# Escorna_CPU_2_20.net
KiCad netlist of a schematic drawn in EAGLE
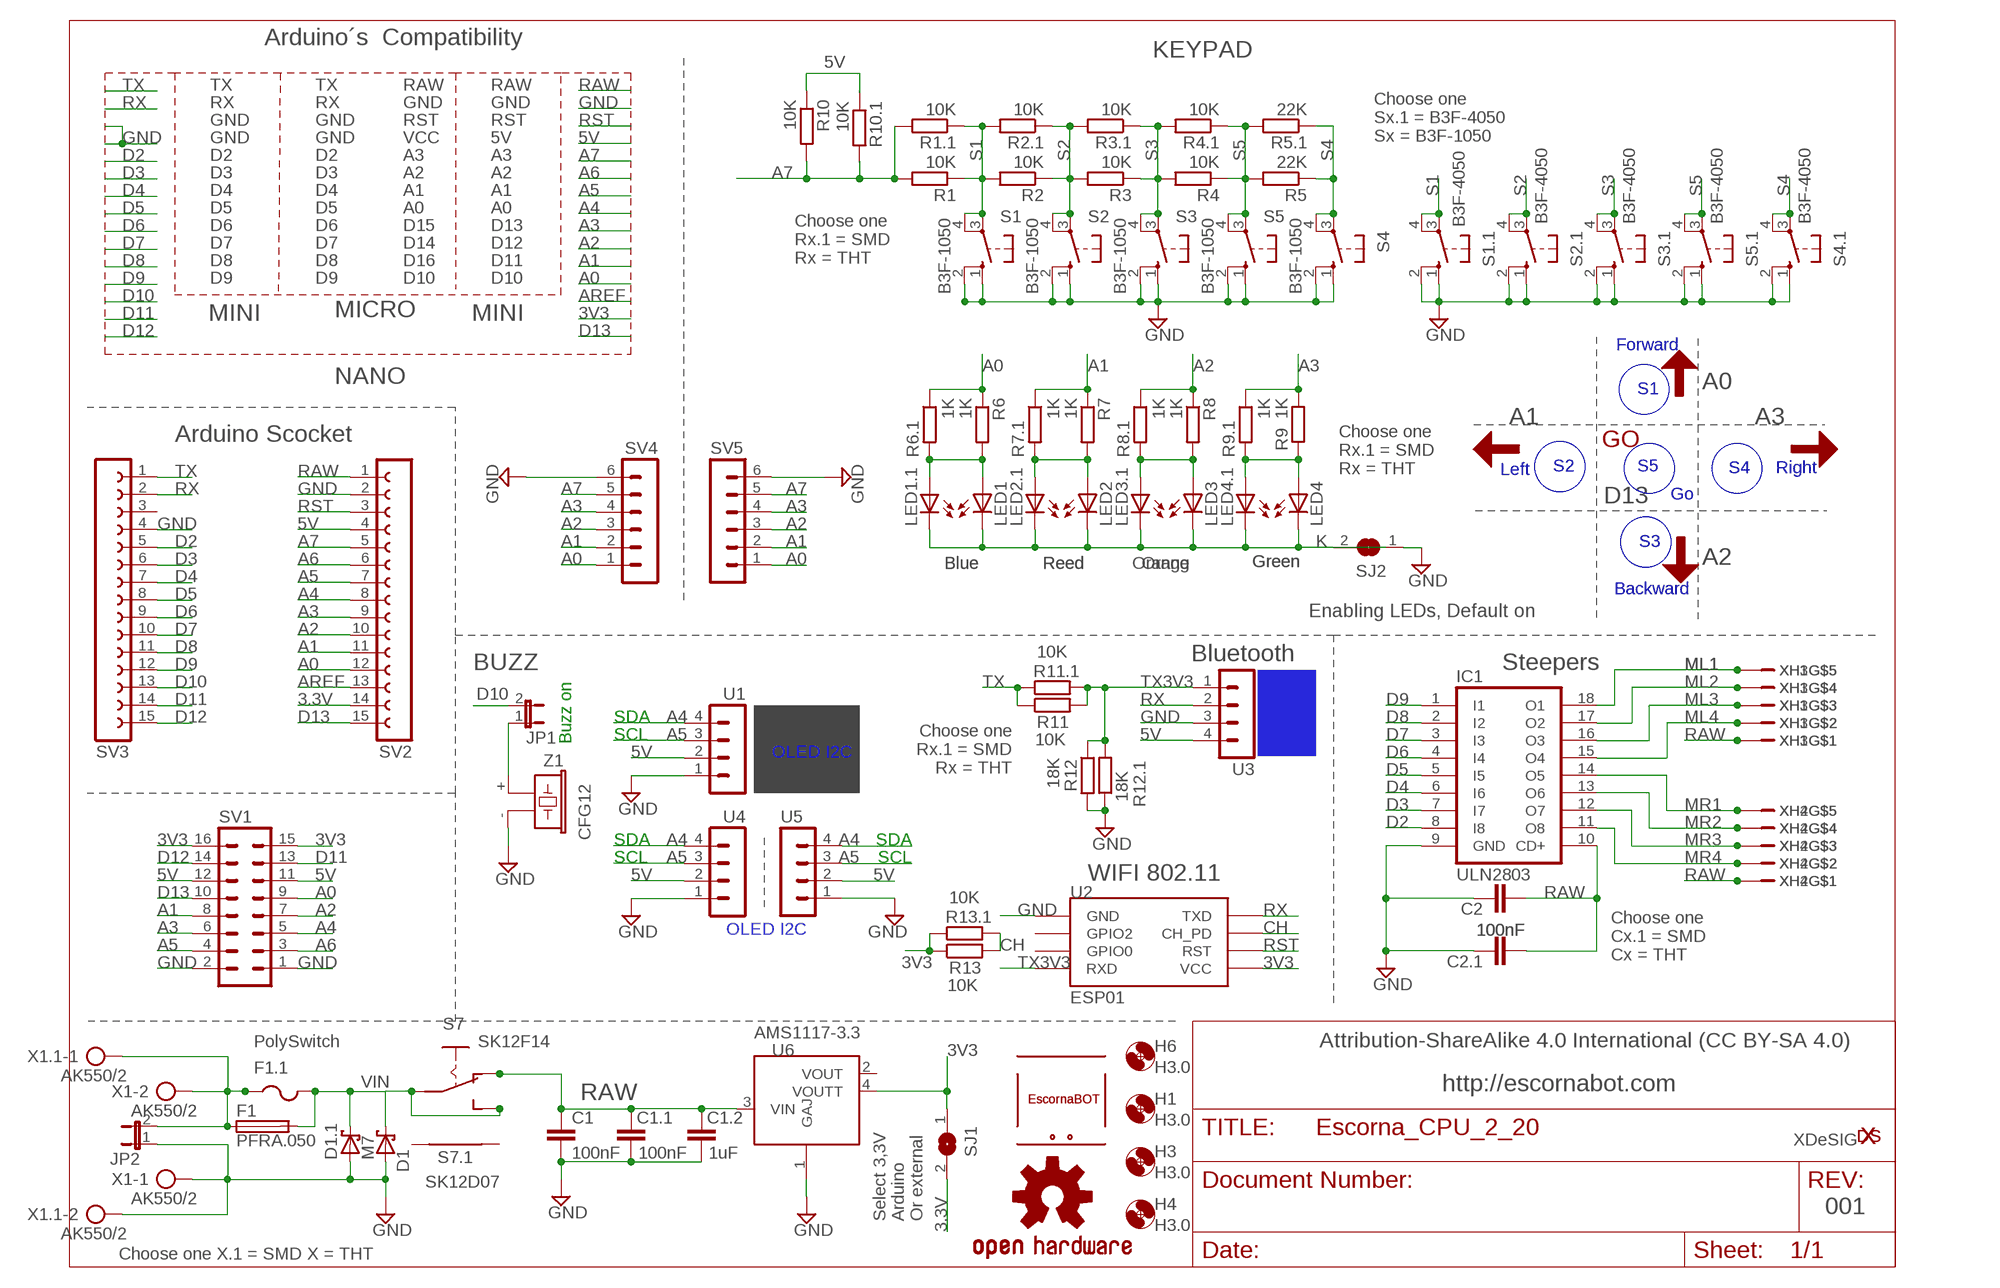
[diagram p0: schematic, sheet 1]

(export (version "E")
  (design (tool "Eeschema 10.0.6"))
  (components
    (comp (ref "C1")
      (value "100nF")
      (footprint "eagle-import:C025-025X050")
      (libsource (lib "eagle-import") (part "C-EU025-025X050"))
    )
    (comp (ref "C1.1")
      (value "100nF")
      (footprint "eagle-import:C0603K")
      (libsource (lib "eagle-import") (part "C-EUC0603K"))
    )
    (comp (ref "C1.2")
      (value "1uF")
      (footprint "eagle-import:C0603K")
      (libsource (lib "eagle-import") (part "C-EUC0603K"))
    )
    (comp (ref "C2")
      (value "100nF")
      (footprint "eagle-import:C025-025X050")
      (libsource (lib "eagle-import") (part "C-EU025-025X050"))
    )
    (comp (ref "C2.1")
      (value "100nF")
      (footprint "eagle-import:C0603K")
      (libsource (lib "eagle-import") (part "C-EUC0603K"))
    )
    (comp (ref "D1")
      (value "1N5817")
      (footprint "eagle-import:DO41-10")
      (libsource (lib "eagle-import") (part "P4KEXX"))
    )
    (comp (ref "D1.1")
      (value "M7")
      (footprint "eagle-import:SMA")
      (libsource (lib "eagle-import") (part "SCHOTTKY-DIODESMA"))
    )
    (comp (ref "ESC1")
      (value "ESCORNABOT")
      (footprint "eagle-import:ESCORNA_PEQUE")
      (libsource (lib "eagle-import") (part "ESCORNABOT"))
    )
    (comp (ref "ESC2")
      (value "ESCORNABOT")
      (footprint "eagle-import:ESCORNA_PEQUE")
      (libsource (lib "eagle-import") (part "ESCORNABOT"))
    )
    (comp (ref "F1")
      (value "PFRA.050")
      (footprint "eagle-import:TE5")
      (libsource (lib "eagle-import") (part "FUSETE5"))
    )
    (comp (ref "F1.1")
      (value "PolySwitch")
      (footprint "eagle-import:R1206")
      (libsource (lib "eagle-import") (part "PTCFUSE-1206"))
    )
    (comp (ref "H1")
      (value "H3.0")
      (footprint "eagle-import:3,0")
      (libsource (lib "eagle-import") (part "MOUNT-HOLE3.0"))
    )
    (comp (ref "H3")
      (value "H3.0")
      (footprint "eagle-import:3,0")
      (libsource (lib "eagle-import") (part "MOUNT-HOLE3.0"))
    )
    (comp (ref "H4")
      (value "H3.0")
      (footprint "eagle-import:3,0")
      (libsource (lib "eagle-import") (part "MOUNT-HOLE3.0"))
    )
    (comp (ref "H6")
      (value "H3.0")
      (footprint "eagle-import:3,0")
      (libsource (lib "eagle-import") (part "MOUNT-HOLE3.0"))
    )
    (comp (ref "IC1")
      (value "ULN2803")
      (footprint "eagle-import:DIL18")
      (libsource (lib "eagle-import") (part "ULN2803A"))
    )
    (comp (ref "JP1")
      (value "JP1E")
      (footprint "eagle-import:1X02")
      (libsource (lib "eagle-import") (part "JP1E"))
    )
    (comp (ref "JP2")
      (value "JP1E")
      (footprint "eagle-import:1X02")
      (libsource (lib "eagle-import") (part "JP1E"))
    )
    (comp (ref "LED1")
      (value "Blue")
      (footprint "eagle-import:LED3MM")
      (libsource (lib "eagle-import") (part "LED3MM"))
    )
    (comp (ref "LED1.1")
      (value "Blue")
      (footprint "eagle-import:CHIPLED_0603")
      (libsource (lib "eagle-import") (part "LEDCHIPLED_0603"))
    )
    (comp (ref "LED2")
      (value "Reed")
      (footprint "eagle-import:LED3MM")
      (libsource (lib "eagle-import") (part "LED3MM"))
    )
    (comp (ref "LED2.1")
      (value "Reed")
      (footprint "eagle-import:CHIPLED_0603")
      (libsource (lib "eagle-import") (part "LEDCHIPLED_0603"))
    )
    (comp (ref "LED3")
      (value "Orange")
      (footprint "eagle-import:LED3MM")
      (libsource (lib "eagle-import") (part "LED3MM"))
    )
    (comp (ref "LED3.1")
      (value "Orang")
      (footprint "eagle-import:CHIPLED_0603")
      (libsource (lib "eagle-import") (part "LEDCHIPLED_0603"))
    )
    (comp (ref "LED4")
      (value "Green")
      (footprint "eagle-import:LED3MM")
      (libsource (lib "eagle-import") (part "LED3MM"))
    )
    (comp (ref "LED4.1")
      (value "Green")
      (footprint "eagle-import:CHIPLED_0603")
      (libsource (lib "eagle-import") (part "LEDCHIPLED_0603"))
    )
    (comp (ref "LOGO2")
      (value "OSHW-LOGOS")
      (footprint "eagle-import:OSHW-LOGO-S")
      (libsource (lib "eagle-import") (part "OSHW-LOGOS"))
    )
    (comp (ref "R1")
      (value "10K")
      (footprint "eagle-import:0204_7")
      (libsource (lib "eagle-import") (part "R-EU_0204/7"))
    )
    (comp (ref "R1.1")
      (value "10K")
      (footprint "eagle-import:R0603")
      (libsource (lib "eagle-import") (part "R-EU_R0603"))
    )
    (comp (ref "R2")
      (value "10K")
      (footprint "eagle-import:0204_7")
      (libsource (lib "eagle-import") (part "R-EU_0204/7"))
    )
    (comp (ref "R2.1")
      (value "10K")
      (footprint "eagle-import:R0603")
      (libsource (lib "eagle-import") (part "R-EU_R0603"))
    )
    (comp (ref "R3")
      (value "10K")
      (footprint "eagle-import:0204_7")
      (libsource (lib "eagle-import") (part "R-EU_0204/7"))
    )
    (comp (ref "R3.1")
      (value "10K")
      (footprint "eagle-import:R0603")
      (libsource (lib "eagle-import") (part "R-EU_R0603"))
    )
    (comp (ref "R4")
      (value "10K")
      (footprint "eagle-import:0204_7")
      (libsource (lib "eagle-import") (part "R-EU_0204/7"))
    )
    (comp (ref "R4.1")
      (value "10K")
      (footprint "eagle-import:R0603")
      (libsource (lib "eagle-import") (part "R-EU_R0603"))
    )
    (comp (ref "R5")
      (value "22K")
      (footprint "eagle-import:0204_7")
      (libsource (lib "eagle-import") (part "R-EU_0204/7"))
    )
    (comp (ref "R5.1")
      (value "22K")
      (footprint "eagle-import:R0603")
      (libsource (lib "eagle-import") (part "R-EU_R0603"))
    )
    (comp (ref "R6")
      (value "1K")
      (footprint "eagle-import:0204_7")
      (libsource (lib "eagle-import") (part "R-EU_0204/7"))
    )
    (comp (ref "R6.1")
      (value "1K")
      (footprint "eagle-import:R0603")
      (libsource (lib "eagle-import") (part "R-EU_R0603"))
    )
    (comp (ref "R7")
      (value "1K")
      (footprint "eagle-import:0204_7")
      (libsource (lib "eagle-import") (part "R-EU_0204/7"))
    )
    (comp (ref "R7.1")
      (value "1K")
      (footprint "eagle-import:R0603")
      (libsource (lib "eagle-import") (part "R-EU_R0603"))
    )
    (comp (ref "R8")
      (value "1K")
      (footprint "eagle-import:0204_7")
      (libsource (lib "eagle-import") (part "R-EU_0204/7"))
    )
    (comp (ref "R8.1")
      (value "1K")
      (footprint "eagle-import:R0603")
      (libsource (lib "eagle-import") (part "R-EU_R0603"))
    )
    (comp (ref "R9")
      (value "1K")
      (footprint "eagle-import:0204_7")
      (libsource (lib "eagle-import") (part "R-EU_0204/7"))
    )
    (comp (ref "R9.1")
      (value "1K")
      (footprint "eagle-import:R0603")
      (libsource (lib "eagle-import") (part "R-EU_R0603"))
    )
    (comp (ref "R10")
      (value "10K")
      (footprint "eagle-import:0204_7")
      (libsource (lib "eagle-import") (part "R-EU_0204/7"))
    )
    (comp (ref "R10.1")
      (value "10K")
      (footprint "eagle-import:R0603")
      (libsource (lib "eagle-import") (part "R-EU_R0603"))
    )
    (comp (ref "R11")
      (value "10K")
      (footprint "eagle-import:0204_7")
      (libsource (lib "eagle-import") (part "R-EU_0204/7"))
    )
    (comp (ref "R11.1")
      (value "10K")
      (footprint "eagle-import:R0603")
      (libsource (lib "eagle-import") (part "R-EU_R0603"))
    )
    (comp (ref "R12")
      (value "18K")
      (footprint "eagle-import:0204_7")
      (libsource (lib "eagle-import") (part "R-EU_0204/7"))
    )
    (comp (ref "R12.1")
      (value "18K")
      (footprint "eagle-import:R0603")
      (libsource (lib "eagle-import") (part "R-EU_R0603"))
    )
    (comp (ref "R13")
      (value "10K")
      (footprint "eagle-import:0204_7")
      (libsource (lib "eagle-import") (part "R-EU_0204/7"))
    )
    (comp (ref "R13.1")
      (value "10K")
      (footprint "eagle-import:R0603")
      (libsource (lib "eagle-import") (part "R-EU_R0603"))
    )
    (comp (ref "S1")
      (value "B3F-1050")
      (footprint "eagle-import:B3F-10XX")
      (fields (field (name "MPN") "B3F-1000"))
      (libsource (lib "eagle-import") (part "10-XX"))
    )
    (comp (ref "S1.1")
      (value "B3F-4050")
      (footprint "eagle-import:B3F-40XX")
      (fields (field (name "MF") "OMRON COMPONENTS USA") (field (name "MPN") "B3F-4000"))
      (libsource (lib "eagle-import") (part "40-XX"))
    )
    (comp (ref "S2")
      (value "B3F-1050")
      (footprint "eagle-import:B3F-10XX")
      (fields (field (name "MPN") "B3F-1000"))
      (libsource (lib "eagle-import") (part "10-XX"))
    )
    (comp (ref "S2.1")
      (value "B3F-4050")
      (footprint "eagle-import:B3F-40XX")
      (fields (field (name "MF") "OMRON COMPONENTS USA") (field (name "MPN") "B3F-4000"))
      (libsource (lib "eagle-import") (part "40-XX"))
    )
    (comp (ref "S3")
      (value "B3F-1050")
      (footprint "eagle-import:B3F-10XX")
      (fields (field (name "MPN") "B3F-1000"))
      (libsource (lib "eagle-import") (part "10-XX"))
    )
    (comp (ref "S3.1")
      (value "B3F-4050")
      (footprint "eagle-import:B3F-40XX")
      (fields (field (name "MF") "OMRON COMPONENTS USA") (field (name "MPN") "B3F-4000"))
      (libsource (lib "eagle-import") (part "40-XX"))
    )
    (comp (ref "S4")
      (value "B3F-1050")
      (footprint "eagle-import:B3F-10XX")
      (fields (field (name "MPN") "B3F-1000"))
      (libsource (lib "eagle-import") (part "10-XX"))
    )
    (comp (ref "S4.1")
      (value "B3F-4050")
      (footprint "eagle-import:B3F-40XX")
      (fields (field (name "MF") "OMRON COMPONENTS USA") (field (name "MPN") "B3F-4000"))
      (libsource (lib "eagle-import") (part "40-XX"))
    )
    (comp (ref "S5")
      (value "B3F-1050")
      (footprint "eagle-import:B3F-10XX")
      (fields (field (name "MPN") "B3F-1000"))
      (libsource (lib "eagle-import") (part "10-XX"))
    )
    (comp (ref "S5.1")
      (value "B3F-4050")
      (footprint "eagle-import:B3F-40XX")
      (fields (field (name "MF") "OMRON COMPONENTS USA") (field (name "MPN") "B3F-4000"))
      (libsource (lib "eagle-import") (part "40-XX"))
    )
    (comp (ref "S7")
      (value "SK12F14")
      (footprint "eagle-import:ESCORNA_SK-12F14-G")
      (libsource (lib "eagle-import") (part "ESCORNA_SK12F14F"))
    )
    (comp (ref "S7.1")
      (value "SK12D07")
      (footprint "eagle-import:ESCORNA_SK-12D07")
      (libsource (lib "eagle-import") (part "ESCORNA_SK12F14D"))
    )
    (comp (ref "SJ1") (value "SJ") (footprint "eagle-import:SJ") (libsource (lib "eagle-import") (part "SJ")))
    (comp (ref "SJ2") (value "SJ") (footprint "eagle-import:SJ") (libsource (lib "eagle-import") (part "SJ")))
    (comp (ref "SV1")
      (value "MA08-2")
      (footprint "eagle-import:MA08-2")
      (libsource (lib "eagle-import") (part "MA08-2"))
    )
    (comp (ref "SV2")
      (value "1x15 SOCKET STRIP")
      (footprint "eagle-import:CON-LSTA_FE15")
      (libsource (lib "eagle-import") (part "CON-LSTA_FE15-1"))
    )
    (comp (ref "SV3")
      (value "1x15 SOCKET STRIP")
      (footprint "eagle-import:CON-LSTA_FE15")
      (libsource (lib "eagle-import") (part "CON-LSTA_FE15-1"))
    )
    (comp (ref "SV4")
      (value "MA06-1")
      (footprint "eagle-import:MA06-1")
      (libsource (lib "eagle-import") (part "MA06-1"))
    )
    (comp (ref "SV5")
      (value "MA06-1")
      (footprint "eagle-import:MA06-1")
      (libsource (lib "eagle-import") (part "MA06-1"))
    )
    (comp (ref "U$1")
      (value "FRECHA")
      (footprint "eagle-import:FRECHA")
      (libsource (lib "eagle-import") (part "FRECHA"))
    )
    (comp (ref "U$2")
      (value "GO")
      (footprint "eagle-import:VALE")
      (libsource (lib "eagle-import") (part "GO"))
    )
    (comp (ref "U$3")
      (value "FRECHA")
      (footprint "eagle-import:FRECHA")
      (libsource (lib "eagle-import") (part "FRECHA"))
    )
    (comp (ref "U$6")
      (value "FRECHA")
      (footprint "eagle-import:FRECHA")
      (libsource (lib "eagle-import") (part "FRECHA"))
    )
    (comp (ref "U$11")
      (value "FRECHA")
      (footprint "eagle-import:FRECHA")
      (libsource (lib "eagle-import") (part "FRECHA"))
    )
    (comp (ref "U$13")
      (value "XDESIG_XDESIG21")
      (footprint "eagle-import:XDESIG_XDESIG")
      (libsource (lib "eagle-import") (part "XDESIG_XDESIG21"))
    )
    (comp (ref "U1")
      (value "MA04-1")
      (footprint "eagle-import:MA04-1")
      (libsource (lib "eagle-import") (part "MA04-1"))
    )
    (comp (ref "U2")
      (value "ESP01")
      (footprint "eagle-import:ESP01")
      (libsource (lib "eagle-import") (part "ESP01"))
    )
    (comp (ref "U3")
      (value "MA04-1")
      (footprint "eagle-import:MA04-1")
      (libsource (lib "eagle-import") (part "MA04-1"))
    )
    (comp (ref "U4")
      (value "MA04-1")
      (footprint "eagle-import:MA04-1")
      (libsource (lib "eagle-import") (part "MA04-1"))
    )
    (comp (ref "U5")
      (value "MA04-1")
      (footprint "eagle-import:MA04-1")
      (libsource (lib "eagle-import") (part "MA04-1"))
    )
    (comp (ref "U6")
      (value "AMS1117-3.3")
      (footprint "eagle-import:SOT223")
      (libsource (lib "eagle-import") (part "ASM1117-3.3"))
    )
    (comp (ref "X1")
      (value "AK550/2")
      (footprint "eagle-import:AK550_2")
      (libsource (lib "eagle-import") (part "AK550/2"))
    )
    (comp (ref "X1.1")
      (value "AK550/2")
      (footprint "eagle-import:AK550_2")
      (fields (field (name "OC_FARNELL") "unknown") (field (name "OC_NEWARK") "unknown"))
      (libsource (lib "eagle-import") (part "AK550/2"))
    )
    (comp (ref "XDS1")
      (value "XDESIG")
      (footprint "eagle-import:XDESIG_CU_2")
      (libsource (lib "eagle-import") (part "XDESIG"))
    )
    (comp (ref "XH1")
      (value "B5B-XH-A")
      (footprint "eagle-import:B5B-XH-A")
      (libsource (lib "eagle-import") (part "B5B-XH-A"))
    )
    (comp (ref "XH2")
      (value "B5B-XH-A")
      (footprint "eagle-import:B5B-XH-A")
      (libsource (lib "eagle-import") (part "B5B-XH-A"))
    )
    (comp (ref "XH3")
      (value "B5B-XH-A")
      (footprint "eagle-import:B5B-XH-A")
      (libsource (lib "eagle-import") (part "B5B-XH-A"))
    )
    (comp (ref "XH4")
      (value "B5B-XH-A")
      (footprint "eagle-import:B5B-XH-A")
      (libsource (lib "eagle-import") (part "B5B-XH-A"))
    )
    (comp (ref "Z1")
      (value "CFG12")
      (footprint "eagle-import:F_CM12P")
      (libsource (lib "eagle-import") (part "F/CM12P"))
    )
  )
  (nets
    (net (code "1") (name "/3.3V") (class "Default")
      (node (ref "SJ1") (pin "2") (pinfunction "2_2") (pintype "passive"))
      (node (ref "SV2") (pin "14") (pinfunction "14_14") (pintype "passive"))
    )
    (net (code "2") (name "/3V3") (class "Default")
      (node (ref "R13") (pin "1") (pinfunction "1_1") (pintype "passive"))
      (node (ref "R13.1") (pin "1") (pinfunction "1_1") (pintype "passive"))
      (node (ref "SJ1") (pin "1") (pinfunction "1_1") (pintype "passive"))
      (node (ref "SV1") (pin "15") (pinfunction "15_15") (pintype "passive"))
      (node (ref "SV1") (pin "16") (pinfunction "16_16") (pintype "passive"))
      (node (ref "U2") (pin "VCC") (pinfunction "VCC_VCC") (pintype "bidirectional"))
      (node (ref "U6") (pin "4") (pinfunction "VOUTT_4") (pintype "bidirectional"))
    )
    (net (code "3") (name "/5V") (class "Default")
      (node (ref "R10") (pin "1") (pinfunction "1_1") (pintype "passive"))
      (node (ref "R10.1") (pin "1") (pinfunction "1_1") (pintype "passive"))
      (node (ref "SV1") (pin "11") (pinfunction "11_11") (pintype "passive"))
      (node (ref "SV1") (pin "12") (pinfunction "12_12") (pintype "passive"))
      (node (ref "SV2") (pin "4") (pinfunction "4_4") (pintype "passive"))
      (node (ref "U1") (pin "2") (pinfunction "2_2") (pintype "passive"))
      (node (ref "U3") (pin "4") (pinfunction "4_4") (pintype "passive"))
      (node (ref "U4") (pin "2") (pinfunction "2_2") (pintype "passive"))
      (node (ref "U5") (pin "2") (pinfunction "2_2") (pintype "passive"))
    )
    (net (code "4") (name "/A0") (class "Default")
      (node (ref "R6") (pin "1") (pinfunction "1_1") (pintype "passive"))
      (node (ref "R6.1") (pin "1") (pinfunction "1_1") (pintype "passive"))
      (node (ref "SV1") (pin "9") (pinfunction "9_9") (pintype "passive"))
      (node (ref "SV2") (pin "12") (pinfunction "12_12") (pintype "passive"))
      (node (ref "SV4") (pin "1") (pinfunction "1_1") (pintype "passive"))
      (node (ref "SV5") (pin "1") (pinfunction "1_1") (pintype "passive"))
    )
    (net (code "5") (name "/A1") (class "Default")
      (node (ref "R7") (pin "1") (pinfunction "1_1") (pintype "passive"))
      (node (ref "R7.1") (pin "1") (pinfunction "1_1") (pintype "passive"))
      (node (ref "SV1") (pin "8") (pinfunction "8_8") (pintype "passive"))
      (node (ref "SV2") (pin "11") (pinfunction "11_11") (pintype "passive"))
      (node (ref "SV4") (pin "2") (pinfunction "2_2") (pintype "passive"))
      (node (ref "SV5") (pin "2") (pinfunction "2_2") (pintype "passive"))
    )
    (net (code "6") (name "/A2") (class "Default")
      (node (ref "R8") (pin "1") (pinfunction "1_1") (pintype "passive"))
      (node (ref "R8.1") (pin "1") (pinfunction "1_1") (pintype "passive"))
      (node (ref "SV1") (pin "7") (pinfunction "7_7") (pintype "passive"))
      (node (ref "SV2") (pin "10") (pinfunction "10_10") (pintype "passive"))
      (node (ref "SV4") (pin "3") (pinfunction "3_3") (pintype "passive"))
      (node (ref "SV5") (pin "3") (pinfunction "3_3") (pintype "passive"))
    )
    (net (code "7") (name "/A3") (class "Default")
      (node (ref "R9") (pin "2") (pinfunction "2_2") (pintype "passive"))
      (node (ref "R9.1") (pin "1") (pinfunction "1_1") (pintype "passive"))
      (node (ref "SV1") (pin "6") (pinfunction "6_6") (pintype "passive"))
      (node (ref "SV2") (pin "9") (pinfunction "9_9") (pintype "passive"))
      (node (ref "SV4") (pin "4") (pinfunction "4_4") (pintype "passive"))
      (node (ref "SV5") (pin "4") (pinfunction "4_4") (pintype "passive"))
    )
    (net (code "8") (name "/A4") (class "Default")
      (node (ref "SV1") (pin "5") (pinfunction "5_5") (pintype "passive"))
      (node (ref "SV2") (pin "8") (pinfunction "8_8") (pintype "passive"))
      (node (ref "U1") (pin "4") (pinfunction "4_4") (pintype "passive"))
      (node (ref "U4") (pin "4") (pinfunction "4_4") (pintype "passive"))
      (node (ref "U5") (pin "4") (pinfunction "4_4") (pintype "passive"))
    )
    (net (code "9") (name "/A5") (class "Default")
      (node (ref "SV1") (pin "4") (pinfunction "4_4") (pintype "passive"))
      (node (ref "SV2") (pin "7") (pinfunction "7_7") (pintype "passive"))
      (node (ref "U1") (pin "3") (pinfunction "3_3") (pintype "passive"))
      (node (ref "U4") (pin "3") (pinfunction "3_3") (pintype "passive"))
      (node (ref "U5") (pin "3") (pinfunction "3_3") (pintype "passive"))
    )
    (net (code "10") (name "/A6") (class "Default")
      (node (ref "SV1") (pin "3") (pinfunction "3_3") (pintype "passive"))
      (node (ref "SV2") (pin "6") (pinfunction "6_6") (pintype "passive"))
    )
    (net (code "11") (name "/A7") (class "Default")
      (node (ref "R1") (pin "2") (pinfunction "2_2") (pintype "passive"))
      (node (ref "R1.1") (pin "2") (pinfunction "2_2") (pintype "passive"))
      (node (ref "R10") (pin "2") (pinfunction "2_2") (pintype "passive"))
      (node (ref "R10.1") (pin "2") (pinfunction "2_2") (pintype "passive"))
      (node (ref "SV2") (pin "5") (pinfunction "5_5") (pintype "passive"))
      (node (ref "SV4") (pin "5") (pinfunction "5_5") (pintype "passive"))
      (node (ref "SV5") (pin "5") (pinfunction "5_5") (pintype "passive"))
    )
    (net (code "12") (name "/AREF") (class "Default")
      (node (ref "SV2") (pin "13") (pinfunction "13_13") (pintype "passive"))
    )
    (net (code "13") (name "/CH") (class "Default")
      (node (ref "R13") (pin "2") (pinfunction "2_2") (pintype "passive"))
      (node (ref "R13.1") (pin "2") (pinfunction "2_2") (pintype "passive"))
      (node (ref "U2") (pin "CH_PD") (pinfunction "CH_PD_CH_PD") (pintype "bidirectional"))
    )
    (net (code "14") (name "/D2") (class "Default")
      (node (ref "IC1") (pin "8") (pinfunction "I8_8") (pintype "input"))
      (node (ref "SV3") (pin "5") (pinfunction "5_5") (pintype "passive"))
    )
    (net (code "15") (name "/D3") (class "Default")
      (node (ref "IC1") (pin "7") (pinfunction "I7_7") (pintype "input"))
      (node (ref "SV3") (pin "6") (pinfunction "6_6") (pintype "passive"))
    )
    (net (code "16") (name "/D4") (class "Default")
      (node (ref "IC1") (pin "6") (pinfunction "I6_6") (pintype "input"))
      (node (ref "SV3") (pin "7") (pinfunction "7_7") (pintype "passive"))
    )
    (net (code "17") (name "/D5") (class "Default")
      (node (ref "IC1") (pin "5") (pinfunction "I5_5") (pintype "input"))
      (node (ref "SV3") (pin "8") (pinfunction "8_8") (pintype "passive"))
    )
    (net (code "18") (name "/D6") (class "Default")
      (node (ref "IC1") (pin "4") (pinfunction "I4_4") (pintype "input"))
      (node (ref "SV3") (pin "9") (pinfunction "9_9") (pintype "passive"))
    )
    (net (code "19") (name "/D7") (class "Default")
      (node (ref "IC1") (pin "3") (pinfunction "I3_3") (pintype "input"))
      (node (ref "SV3") (pin "10") (pinfunction "10_10") (pintype "passive"))
    )
    (net (code "20") (name "/D8") (class "Default")
      (node (ref "IC1") (pin "2") (pinfunction "I2_2") (pintype "input"))
      (node (ref "SV3") (pin "11") (pinfunction "11_11") (pintype "passive"))
    )
    (net (code "21") (name "/D9") (class "Default")
      (node (ref "IC1") (pin "1") (pinfunction "I1_1") (pintype "input"))
      (node (ref "SV3") (pin "12") (pinfunction "12_12") (pintype "passive"))
    )
    (net (code "22") (name "/D10") (class "Default")
      (node (ref "JP1") (pin "2") (pinfunction "2_2") (pintype "passive"))
      (node (ref "SV3") (pin "13") (pinfunction "13_13") (pintype "passive"))
    )
    (net (code "23") (name "/D11") (class "Default")
      (node (ref "SV1") (pin "13") (pinfunction "13_13") (pintype "passive"))
      (node (ref "SV3") (pin "14") (pinfunction "14_14") (pintype "passive"))
    )
    (net (code "24") (name "/D12") (class "Default")
      (node (ref "SV1") (pin "14") (pinfunction "14_14") (pintype "passive"))
      (node (ref "SV3") (pin "15") (pinfunction "15_15") (pintype "passive"))
    )
    (net (code "25") (name "/D13") (class "Default")
      (node (ref "SV1") (pin "10") (pinfunction "10_10") (pintype "passive"))
      (node (ref "SV2") (pin "15") (pinfunction "15_15") (pintype "passive"))
    )
    (net (code "26") (name "/K") (class "Default")
      (node (ref "LED1") (pin "K") (pinfunction "C_K") (pintype "passive"))
      (node (ref "LED1.1") (pin "C") (pinfunction "C_C") (pintype "passive"))
      (node (ref "LED2") (pin "K") (pinfunction "C_K") (pintype "passive"))
      (node (ref "LED2.1") (pin "C") (pinfunction "C_C") (pintype "passive"))
      (node (ref "LED3") (pin "K") (pinfunction "C_K") (pintype "passive"))
      (node (ref "LED3.1") (pin "C") (pinfunction "C_C") (pintype "passive"))
      (node (ref "LED4") (pin "K") (pinfunction "C_K") (pintype "passive"))
      (node (ref "LED4.1") (pin "C") (pinfunction "C_C") (pintype "passive"))
      (node (ref "SJ2") (pin "2") (pinfunction "2_2") (pintype "passive"))
    )
    (net (code "27") (name "/ML1") (class "Default")
      (node (ref "IC1") (pin "18") (pinfunction "O1_18") (pintype "open_collector"))
      (node (ref "XH1") (pin "P$5") (pinfunction "1_P$5") (pintype "passive"))
      (node (ref "XH3") (pin "P$5") (pinfunction "1_P$5") (pintype "passive"))
    )
    (net (code "28") (name "/ML2") (class "Default")
      (node (ref "IC1") (pin "17") (pinfunction "O2_17") (pintype "open_collector"))
      (node (ref "XH1") (pin "P$4") (pinfunction "1_P$4") (pintype "passive"))
      (node (ref "XH3") (pin "P$4") (pinfunction "1_P$4") (pintype "passive"))
    )
    (net (code "29") (name "/ML3") (class "Default")
      (node (ref "IC1") (pin "16") (pinfunction "O3_16") (pintype "open_collector"))
      (node (ref "XH1") (pin "P$3") (pinfunction "1_P$3") (pintype "passive"))
      (node (ref "XH3") (pin "P$3") (pinfunction "1_P$3") (pintype "passive"))
    )
    (net (code "30") (name "/ML4") (class "Default")
      (node (ref "IC1") (pin "15") (pinfunction "O4_15") (pintype "open_collector"))
      (node (ref "XH1") (pin "P$2") (pinfunction "1_P$2") (pintype "passive"))
      (node (ref "XH3") (pin "P$2") (pinfunction "1_P$2") (pintype "passive"))
    )
    (net (code "31") (name "/MR1") (class "Default")
      (node (ref "IC1") (pin "14") (pinfunction "O5_14") (pintype "open_collector"))
      (node (ref "XH2") (pin "P$5") (pinfunction "1_P$5") (pintype "passive"))
      (node (ref "XH4") (pin "P$5") (pinfunction "1_P$5") (pintype "passive"))
    )
    (net (code "32") (name "/MR2") (class "Default")
      (node (ref "IC1") (pin "13") (pinfunction "O6_13") (pintype "open_collector"))
      (node (ref "XH2") (pin "P$4") (pinfunction "1_P$4") (pintype "passive"))
      (node (ref "XH4") (pin "P$4") (pinfunction "1_P$4") (pintype "passive"))
    )
    (net (code "33") (name "/MR3") (class "Default")
      (node (ref "IC1") (pin "12") (pinfunction "O7_12") (pintype "open_collector"))
      (node (ref "XH2") (pin "P$3") (pinfunction "1_P$3") (pintype "passive"))
      (node (ref "XH4") (pin "P$3") (pinfunction "1_P$3") (pintype "passive"))
    )
    (net (code "34") (name "/MR4") (class "Default")
      (node (ref "IC1") (pin "11") (pinfunction "O8_11") (pintype "open_collector"))
      (node (ref "XH2") (pin "P$2") (pinfunction "1_P$2") (pintype "passive"))
      (node (ref "XH4") (pin "P$2") (pinfunction "1_P$2") (pintype "passive"))
    )
    (net (code "35") (name "/RAW") (class "Default")
      (node (ref "C1") (pin "1") (pinfunction "1_1") (pintype "passive"))
      (node (ref "C1.1") (pin "2") (pinfunction "2_2") (pintype "passive"))
      (node (ref "C1.2") (pin "2") (pinfunction "2_2") (pintype "passive"))
      (node (ref "C2") (pin "2") (pinfunction "2_2") (pintype "passive"))
      (node (ref "C2.1") (pin "2") (pinfunction "2_2") (pintype "passive"))
      (node (ref "IC1") (pin "10") (pinfunction "CD+_10") (pintype "passive"))
      (node (ref "S7") (pin "P$2") (pinfunction "O_P$2") (pintype "passive"))
      (node (ref "S7.1") (pin "P$2") (pinfunction "O_P$2") (pintype "passive"))
      (node (ref "SV2") (pin "1") (pinfunction "1_1") (pintype "passive"))
      (node (ref "U6") (pin "3") (pinfunction "VIN_3") (pintype "bidirectional"))
      (node (ref "XH1") (pin "P$1") (pinfunction "1_P$1") (pintype "passive"))
      (node (ref "XH2") (pin "P$1") (pinfunction "1_P$1") (pintype "passive"))
      (node (ref "XH3") (pin "P$1") (pinfunction "1_P$1") (pintype "passive"))
      (node (ref "XH4") (pin "P$1") (pinfunction "1_P$1") (pintype "passive"))
    )
    (net (code "36") (name "/RST") (class "Default")
      (node (ref "SV2") (pin "3") (pinfunction "3_3") (pintype "passive"))
      (node (ref "U2") (pin "RST") (pinfunction "RST_RST") (pintype "bidirectional"))
    )
    (net (code "37") (name "/RX") (class "Default")
      (node (ref "SV3") (pin "2") (pinfunction "2_2") (pintype "passive"))
      (node (ref "U2") (pin "TX") (pinfunction "TXD_TX") (pintype "bidirectional"))
      (node (ref "U3") (pin "2") (pinfunction "2_2") (pintype "passive"))
    )
    (net (code "38") (name "/S1") (class "Default")
      (node (ref "R1") (pin "1") (pinfunction "1_1") (pintype "passive"))
      (node (ref "R1.1") (pin "1") (pinfunction "1_1") (pintype "passive"))
      (node (ref "R2") (pin "2") (pinfunction "2_2") (pintype "passive"))
      (node (ref "R2.1") (pin "2") (pinfunction "2_2") (pintype "passive"))
      (node (ref "S1") (pin "3") (pinfunction "P_3") (pintype "passive"))
      (node (ref "S1") (pin "4") (pinfunction "P1_4") (pintype "passive"))
      (node (ref "S1.1") (pin "3") (pinfunction "P_3") (pintype "passive"))
      (node (ref "S1.1") (pin "4") (pinfunction "P1_4") (pintype "passive"))
    )
    (net (code "39") (name "/S2") (class "Default")
      (node (ref "R2") (pin "1") (pinfunction "1_1") (pintype "passive"))
      (node (ref "R2.1") (pin "1") (pinfunction "1_1") (pintype "passive"))
      (node (ref "R3") (pin "2") (pinfunction "2_2") (pintype "passive"))
      (node (ref "R3.1") (pin "2") (pinfunction "2_2") (pintype "passive"))
      (node (ref "S2") (pin "3") (pinfunction "P_3") (pintype "passive"))
      (node (ref "S2") (pin "4") (pinfunction "P1_4") (pintype "passive"))
      (node (ref "S2.1") (pin "3") (pinfunction "P_3") (pintype "passive"))
      (node (ref "S2.1") (pin "4") (pinfunction "P1_4") (pintype "passive"))
    )
    (net (code "40") (name "/S3") (class "Default")
      (node (ref "R3") (pin "1") (pinfunction "1_1") (pintype "passive"))
      (node (ref "R3.1") (pin "1") (pinfunction "1_1") (pintype "passive"))
      (node (ref "R4") (pin "2") (pinfunction "2_2") (pintype "passive"))
      (node (ref "R4.1") (pin "2") (pinfunction "2_2") (pintype "passive"))
      (node (ref "S3") (pin "3") (pinfunction "P_3") (pintype "passive"))
      (node (ref "S3") (pin "4") (pinfunction "P1_4") (pintype "passive"))
      (node (ref "S3.1") (pin "3") (pinfunction "P_3") (pintype "passive"))
      (node (ref "S3.1") (pin "4") (pinfunction "P1_4") (pintype "passive"))
    )
    (net (code "41") (name "/S4") (class "Default")
      (node (ref "R5") (pin "1") (pinfunction "1_1") (pintype "passive"))
      (node (ref "R5.1") (pin "1") (pinfunction "1_1") (pintype "passive"))
      (node (ref "S4") (pin "3") (pinfunction "P_3") (pintype "passive"))
      (node (ref "S4") (pin "4") (pinfunction "P1_4") (pintype "passive"))
      (node (ref "S4.1") (pin "3") (pinfunction "P_3") (pintype "passive"))
      (node (ref "S4.1") (pin "4") (pinfunction "P1_4") (pintype "passive"))
    )
    (net (code "42") (name "/S5") (class "Default")
      (node (ref "R4") (pin "1") (pinfunction "1_1") (pintype "passive"))
      (node (ref "R4.1") (pin "1") (pinfunction "1_1") (pintype "passive"))
      (node (ref "R5") (pin "2") (pinfunction "2_2") (pintype "passive"))
      (node (ref "R5.1") (pin "2") (pinfunction "2_2") (pintype "passive"))
      (node (ref "S5") (pin "3") (pinfunction "P_3") (pintype "passive"))
      (node (ref "S5") (pin "4") (pinfunction "P1_4") (pintype "passive"))
      (node (ref "S5.1") (pin "3") (pinfunction "P_3") (pintype "passive"))
      (node (ref "S5.1") (pin "4") (pinfunction "P1_4") (pintype "passive"))
    )
    (net (code "43") (name "/TX") (class "Default")
      (node (ref "R11") (pin "1") (pinfunction "1_1") (pintype "passive"))
      (node (ref "R11.1") (pin "1") (pinfunction "1_1") (pintype "passive"))
      (node (ref "SV3") (pin "1") (pinfunction "1_1") (pintype "passive"))
    )
    (net (code "44") (name "/TX3V3") (class "Default")
      (node (ref "R11") (pin "2") (pinfunction "2_2") (pintype "passive"))
      (node (ref "R11.1") (pin "2") (pinfunction "2_2") (pintype "passive"))
      (node (ref "R12") (pin "1") (pinfunction "1_1") (pintype "passive"))
      (node (ref "R12.1") (pin "2") (pinfunction "2_2") (pintype "passive"))
      (node (ref "U2") (pin "RX") (pinfunction "RXD_RX") (pintype "bidirectional"))
      (node (ref "U3") (pin "1") (pinfunction "1_1") (pintype "passive"))
    )
    (net (code "45") (name "/VIN") (class "Default")
      (node (ref "D1") (pin "C") (pinfunction "C_C") (pintype "passive"))
      (node (ref "D1.1") (pin "C") (pinfunction "C_C") (pintype "passive"))
      (node (ref "F1") (pin "2") (pinfunction "2_2") (pintype "passive"))
      (node (ref "F1.1") (pin "2") (pinfunction "2_2") (pintype "passive"))
      (node (ref "S7") (pin "P$1") (pinfunction "P_P$1") (pintype "passive"))
      (node (ref "S7") (pin "P$3") (pinfunction "S_P$3") (pintype "passive"))
      (node (ref "S7.1") (pin "P$1") (pinfunction "P_P$1") (pintype "passive"))
      (node (ref "S7.1") (pin "P$3") (pinfunction "S_P$3") (pintype "passive"))
    )
    (net (code "46") (name "GND") (class "Default")
      (node (ref "C1") (pin "2") (pinfunction "2_2") (pintype "passive"))
      (node (ref "C1.1") (pin "1") (pinfunction "1_1") (pintype "passive"))
      (node (ref "C1.2") (pin "1") (pinfunction "1_1") (pintype "passive"))
      (node (ref "C2") (pin "1") (pinfunction "1_1") (pintype "passive"))
      (node (ref "C2.1") (pin "1") (pinfunction "1_1") (pintype "passive"))
      (node (ref "D1") (pin "A") (pinfunction "A_A") (pintype "passive"))
      (node (ref "D1.1") (pin "A") (pinfunction "A_A") (pintype "passive"))
      (node (ref "IC1") (pin "9") (pinfunction "GND_9") (pintype "power_in"))
      (node (ref "JP2") (pin "1") (pinfunction "1_1") (pintype "passive"))
      (node (ref "R12") (pin "2") (pinfunction "2_2") (pintype "passive"))
      (node (ref "R12.1") (pin "1") (pinfunction "1_1") (pintype "passive"))
      (node (ref "S1") (pin "1") (pinfunction "S_1") (pintype "passive"))
      (node (ref "S1") (pin "2") (pinfunction "S1_2") (pintype "passive"))
      (node (ref "S1.1") (pin "1") (pinfunction "S_1") (pintype "passive"))
      (node (ref "S1.1") (pin "2") (pinfunction "S1_2") (pintype "passive"))
      (node (ref "S2") (pin "1") (pinfunction "S_1") (pintype "passive"))
      (node (ref "S2") (pin "2") (pinfunction "S1_2") (pintype "passive"))
      (node (ref "S2.1") (pin "1") (pinfunction "S_1") (pintype "passive"))
      (node (ref "S2.1") (pin "2") (pinfunction "S1_2") (pintype "passive"))
      (node (ref "S3") (pin "1") (pinfunction "S_1") (pintype "passive"))
      (node (ref "S3") (pin "2") (pinfunction "S1_2") (pintype "passive"))
      (node (ref "S3.1") (pin "1") (pinfunction "S_1") (pintype "passive"))
      (node (ref "S3.1") (pin "2") (pinfunction "S1_2") (pintype "passive"))
      (node (ref "S4") (pin "1") (pinfunction "S_1") (pintype "passive"))
      (node (ref "S4") (pin "2") (pinfunction "S1_2") (pintype "passive"))
      (node (ref "S4.1") (pin "1") (pinfunction "S_1") (pintype "passive"))
      (node (ref "S4.1") (pin "2") (pinfunction "S1_2") (pintype "passive"))
      (node (ref "S5") (pin "1") (pinfunction "S_1") (pintype "passive"))
      (node (ref "S5") (pin "2") (pinfunction "S1_2") (pintype "passive"))
      (node (ref "S5.1") (pin "1") (pinfunction "S_1") (pintype "passive"))
      (node (ref "S5.1") (pin "2") (pinfunction "S1_2") (pintype "passive"))
      (node (ref "SJ2") (pin "1") (pinfunction "1_1") (pintype "passive"))
      (node (ref "SV1") (pin "1") (pinfunction "1_1") (pintype "passive"))
      (node (ref "SV1") (pin "2") (pinfunction "2_2") (pintype "passive"))
      (node (ref "SV2") (pin "2") (pinfunction "2_2") (pintype "passive"))
      (node (ref "SV3") (pin "4") (pinfunction "4_4") (pintype "passive"))
      (node (ref "SV4") (pin "6") (pinfunction "6_6") (pintype "passive"))
      (node (ref "SV5") (pin "6") (pinfunction "6_6") (pintype "passive"))
      (node (ref "U1") (pin "1") (pinfunction "1_1") (pintype "passive"))
      (node (ref "U2") (pin "GND") (pinfunction "GND_GND") (pintype "bidirectional"))
      (node (ref "U3") (pin "3") (pinfunction "3_3") (pintype "passive"))
      (node (ref "U4") (pin "1") (pinfunction "1_1") (pintype "passive"))
      (node (ref "U5") (pin "1") (pinfunction "1_1") (pintype "passive"))
      (node (ref "U6") (pin "1") (pinfunction "GAJ_1") (pintype "bidirectional"))
      (node (ref "X1") (pin "1") (pinfunction "KL_1") (pintype "passive"))
      (node (ref "X1.1") (pin "2") (pinfunction "KL_2") (pintype "passive"))
      (node (ref "Z1") (pin "-") (pinfunction "2_-") (pintype "passive"))
    )
    (net (code "47") (name "Net-(LED1-PadA)") (class "Default")
      (node (ref "LED1") (pin "A") (pinfunction "A_A") (pintype "passive"))
      (node (ref "LED1.1") (pin "A") (pinfunction "A_A") (pintype "passive"))
      (node (ref "R6") (pin "2") (pinfunction "2_2") (pintype "passive"))
      (node (ref "R6.1") (pin "2") (pinfunction "2_2") (pintype "passive"))
    )
    (net (code "48") (name "Net-(LED2-PadA)") (class "Default")
      (node (ref "LED2") (pin "A") (pinfunction "A_A") (pintype "passive"))
      (node (ref "LED2.1") (pin "A") (pinfunction "A_A") (pintype "passive"))
      (node (ref "R7") (pin "2") (pinfunction "2_2") (pintype "passive"))
      (node (ref "R7.1") (pin "2") (pinfunction "2_2") (pintype "passive"))
    )
    (net (code "49") (name "Net-(LED3-PadA)") (class "Default")
      (node (ref "LED3") (pin "A") (pinfunction "A_A") (pintype "passive"))
      (node (ref "LED3.1") (pin "A") (pinfunction "A_A") (pintype "passive"))
      (node (ref "R8") (pin "2") (pinfunction "2_2") (pintype "passive"))
      (node (ref "R8.1") (pin "2") (pinfunction "2_2") (pintype "passive"))
    )
    (net (code "50") (name "Net-(LED4-PadA)") (class "Default")
      (node (ref "LED4") (pin "A") (pinfunction "A_A") (pintype "passive"))
      (node (ref "LED4.1") (pin "A") (pinfunction "A_A") (pintype "passive"))
      (node (ref "R9") (pin "1") (pinfunction "1_1") (pintype "passive"))
      (node (ref "R9.1") (pin "2") (pinfunction "2_2") (pintype "passive"))
    )
    (net (code "51") (name "Net-(S7-P$1)") (class "Default")
      (node (ref "S7") (pin "P$4") (pinfunction "P$1_P$4") (pintype "passive"))
      (node (ref "S7.1") (pin "P$4") (pinfunction "P$1_P$4") (pintype "passive"))
    )
    (net (code "52") (name "Net-(S7-P$2)") (class "Default")
      (node (ref "S7") (pin "P$5") (pinfunction "P$2_P$5") (pintype "bidirectional"))
      (node (ref "S7.1") (pin "P$5") (pinfunction "P$2_P$5") (pintype "bidirectional"))
    )
    (net (code "53") (name "Net-(X1.1A-KL)") (class "Default")
      (node (ref "F1") (pin "1") (pinfunction "1_1") (pintype "passive"))
      (node (ref "F1.1") (pin "1") (pinfunction "1_1") (pintype "passive"))
      (node (ref "JP2") (pin "2") (pinfunction "2_2") (pintype "passive"))
      (node (ref "X1") (pin "2") (pinfunction "KL_2") (pintype "passive"))
      (node (ref "X1.1") (pin "1") (pinfunction "KL_1") (pintype "passive"))
    )
    (net (code "54") (name "Net-(Z1-1)") (class "Default")
      (node (ref "JP1") (pin "1") (pinfunction "1_1") (pintype "passive"))
      (node (ref "Z1") (pin "+") (pinfunction "1_+") (pintype "passive"))
    )
    (net (code "55") (name "unconnected-(SV3-Pad3)") (class "Default")
      (node (ref "SV3") (pin "3") (pinfunction "3_3") (pintype "passive"))
    )
    (net (code "56") (name "unconnected-(U2-PadGPIO0)") (class "Default")
      (node (ref "U2") (pin "GPIO0") (pinfunction "GPIO0_GPIO0") (pintype "bidirectional"))
    )
    (net (code "57") (name "unconnected-(U2-PadGPIO2)") (class "Default")
      (node (ref "U2") (pin "GPIO2") (pinfunction "GPIO2_GPIO2") (pintype "bidirectional"))
    )
    (net (code "58") (name "unconnected-(U6-VOUT-Pad2)") (class "Default")
      (node (ref "U6") (pin "2") (pinfunction "VOUT_2") (pintype "bidirectional"))
    )
  )
)
